# 08_IO.net
KiCad netlist of a schematic drawn in Altium Designer
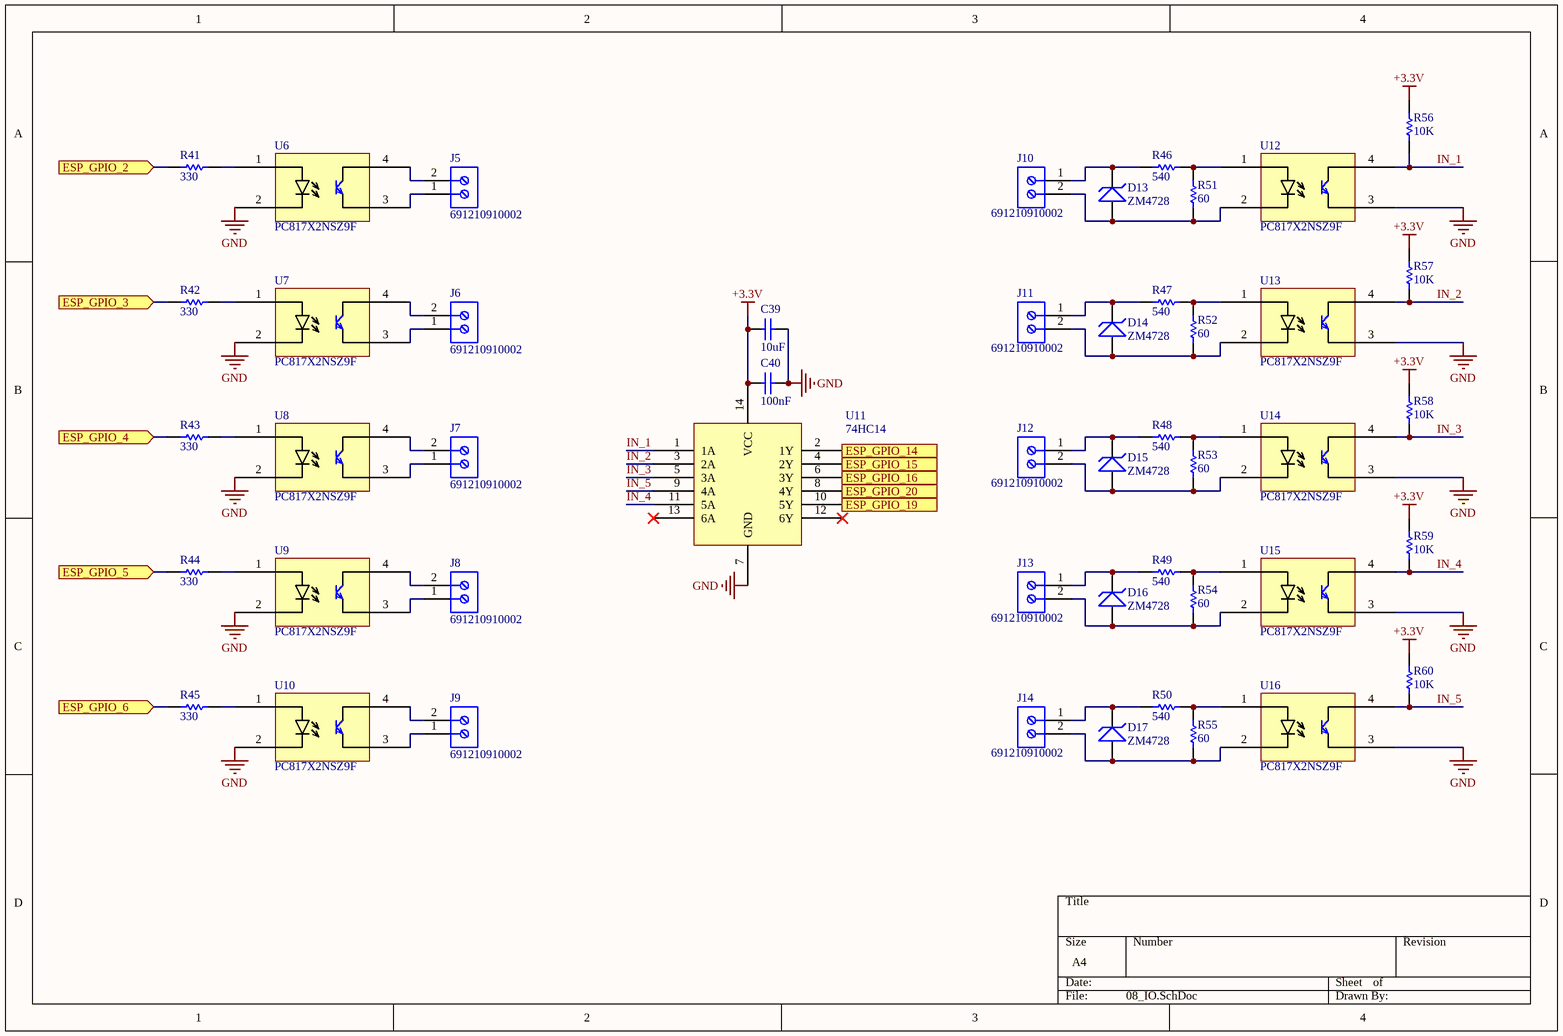
[diagram p0: 08_IO.SchDoc]

(export (version "E")
  (design (tool "Eeschema 10.0.6"))
  (components
    (comp (ref "C39")
      (value "10uF")
      (footprint "C0402")
      (fields (field (name "Comment") "Capacitor"))
      (libsource (lib "MiclsLib") (part "Capacitor"))
    )
    (comp (ref "C40")
      (value "100nF")
      (footprint "C0402")
      (fields (field (name "Comment") "Capacitor"))
      (libsource (lib "MiclsLib") (part "Capacitor"))
    )
    (comp (ref "D13")
      (value "ZM4728")
      (footprint "DIOMELF3515N")
      (libsource (lib "MiclsLib") (part "ZM4728"))
    )
    (comp (ref "D14")
      (value "ZM4728")
      (footprint "DIOMELF3515N")
      (libsource (lib "MiclsLib") (part "ZM4728"))
    )
    (comp (ref "D15")
      (value "ZM4728")
      (footprint "DIOMELF3515N")
      (libsource (lib "MiclsLib") (part "ZM4728"))
    )
    (comp (ref "D16")
      (value "ZM4728")
      (footprint "DIOMELF3515N")
      (libsource (lib "MiclsLib") (part "ZM4728"))
    )
    (comp (ref "D17")
      (value "ZM4728")
      (footprint "DIOMELF3515N")
      (libsource (lib "MiclsLib") (part "ZM4728"))
    )
    (comp (ref "J5")
      (value "691210910002")
      (footprint "691210910002")
      (description "WR-TBL Serie 2109 Horizontal Entry, Rising Cage Clamp, pitch 2.54mm, 2p")
      (fields (field (name "PUBLISHER") "Wurth Elektronik"))
      (libsource (lib "691322310002.") (part "691210910002"))
    )
    (comp (ref "J6")
      (value "691210910002")
      (footprint "691210910002")
      (description "WR-TBL Serie 2109 Horizontal Entry, Rising Cage Clamp, pitch 2.54mm, 2p")
      (fields (field (name "PUBLISHER") "Wurth Elektronik"))
      (libsource (lib "691322310002.") (part "691210910002"))
    )
    (comp (ref "J7")
      (value "691210910002")
      (footprint "691210910002")
      (description "WR-TBL Serie 2109 Horizontal Entry, Rising Cage Clamp, pitch 2.54mm, 2p")
      (fields (field (name "PUBLISHER") "Wurth Elektronik"))
      (libsource (lib "691322310002.") (part "691210910002"))
    )
    (comp (ref "J8")
      (value "691210910002")
      (footprint "691210910002")
      (description "WR-TBL Serie 2109 Horizontal Entry, Rising Cage Clamp, pitch 2.54mm, 2p")
      (fields (field (name "PUBLISHER") "Wurth Elektronik"))
      (libsource (lib "691322310002.") (part "691210910002"))
    )
    (comp (ref "J9")
      (value "691210910002")
      (footprint "691210910002")
      (description "WR-TBL Serie 2109 Horizontal Entry, Rising Cage Clamp, pitch 2.54mm, 2p")
      (fields (field (name "PUBLISHER") "Wurth Elektronik"))
      (libsource (lib "691322310002.") (part "691210910002"))
    )
    (comp (ref "J10")
      (value "691210910002")
      (footprint "691210910002")
      (description "WR-TBL Serie 2109 Horizontal Entry, Rising Cage Clamp, pitch 2.54mm, 2p")
      (fields (field (name "PUBLISHER") "Wurth Elektronik"))
      (libsource (lib "691322310002.") (part "691210910002"))
    )
    (comp (ref "J11")
      (value "691210910002")
      (footprint "691210910002")
      (description "WR-TBL Serie 2109 Horizontal Entry, Rising Cage Clamp, pitch 2.54mm, 2p")
      (fields (field (name "PUBLISHER") "Wurth Elektronik"))
      (libsource (lib "691322310002.") (part "691210910002"))
    )
    (comp (ref "J12")
      (value "691210910002")
      (footprint "691210910002")
      (description "WR-TBL Serie 2109 Horizontal Entry, Rising Cage Clamp, pitch 2.54mm, 2p")
      (fields (field (name "PUBLISHER") "Wurth Elektronik"))
      (libsource (lib "691322310002.") (part "691210910002"))
    )
    (comp (ref "J13")
      (value "691210910002")
      (footprint "691210910002")
      (description "WR-TBL Serie 2109 Horizontal Entry, Rising Cage Clamp, pitch 2.54mm, 2p")
      (fields (field (name "PUBLISHER") "Wurth Elektronik"))
      (libsource (lib "691322310002.") (part "691210910002"))
    )
    (comp (ref "J14")
      (value "691210910002")
      (footprint "691210910002")
      (description "WR-TBL Serie 2109 Horizontal Entry, Rising Cage Clamp, pitch 2.54mm, 2p")
      (fields (field (name "PUBLISHER") "Wurth Elektronik"))
      (libsource (lib "691322310002.") (part "691210910002"))
    )
    (comp (ref "R41")
      (value "330")
      (footprint "R0402")
      (fields (field (name "Comment") "Resistor"))
      (libsource (lib "MiclsLib") (part "Resistor"))
    )
    (comp (ref "R42")
      (value "330")
      (footprint "R0402")
      (fields (field (name "Comment") "Resistor"))
      (libsource (lib "MiclsLib") (part "Resistor"))
    )
    (comp (ref "R43")
      (value "330")
      (footprint "R0402")
      (fields (field (name "Comment") "Resistor"))
      (libsource (lib "MiclsLib") (part "Resistor"))
    )
    (comp (ref "R44")
      (value "330")
      (footprint "R0402")
      (fields (field (name "Comment") "Resistor"))
      (libsource (lib "MiclsLib") (part "Resistor"))
    )
    (comp (ref "R45")
      (value "330")
      (footprint "R0402")
      (fields (field (name "Comment") "Resistor"))
      (libsource (lib "MiclsLib") (part "Resistor"))
    )
    (comp (ref "R46")
      (value "540")
      (footprint "R0402")
      (fields (field (name "Comment") "Resistor"))
      (libsource (lib "MiclsLib") (part "Resistor"))
    )
    (comp (ref "R47")
      (value "540")
      (footprint "R0402")
      (fields (field (name "Comment") "Resistor"))
      (libsource (lib "MiclsLib") (part "Resistor"))
    )
    (comp (ref "R48")
      (value "540")
      (footprint "R0402")
      (fields (field (name "Comment") "Resistor"))
      (libsource (lib "MiclsLib") (part "Resistor"))
    )
    (comp (ref "R49")
      (value "540")
      (footprint "R0402")
      (fields (field (name "Comment") "Resistor"))
      (libsource (lib "MiclsLib") (part "Resistor"))
    )
    (comp (ref "R50")
      (value "540")
      (footprint "R0402")
      (fields (field (name "Comment") "Resistor"))
      (libsource (lib "MiclsLib") (part "Resistor"))
    )
    (comp (ref "R51")
      (value "60")
      (footprint "R0402")
      (fields (field (name "Comment") "Resistor"))
      (libsource (lib "MiclsLib") (part "Resistor"))
    )
    (comp (ref "R52")
      (value "60")
      (footprint "R0402")
      (fields (field (name "Comment") "Resistor"))
      (libsource (lib "MiclsLib") (part "Resistor"))
    )
    (comp (ref "R53")
      (value "60")
      (footprint "R0402")
      (fields (field (name "Comment") "Resistor"))
      (libsource (lib "MiclsLib") (part "Resistor"))
    )
    (comp (ref "R54")
      (value "60")
      (footprint "R0402")
      (fields (field (name "Comment") "Resistor"))
      (libsource (lib "MiclsLib") (part "Resistor"))
    )
    (comp (ref "R55")
      (value "60")
      (footprint "R0402")
      (fields (field (name "Comment") "Resistor"))
      (libsource (lib "MiclsLib") (part "Resistor"))
    )
    (comp (ref "R56")
      (value "10K")
      (footprint "R0402")
      (fields (field (name "Comment") "Resistor"))
      (libsource (lib "MiclsLib") (part "Resistor"))
    )
    (comp (ref "R57")
      (value "10K")
      (footprint "R0402")
      (fields (field (name "Comment") "Resistor"))
      (libsource (lib "MiclsLib") (part "Resistor"))
    )
    (comp (ref "R58")
      (value "10K")
      (footprint "R0402")
      (fields (field (name "Comment") "Resistor"))
      (libsource (lib "MiclsLib") (part "Resistor"))
    )
    (comp (ref "R59")
      (value "10K")
      (footprint "R0402")
      (fields (field (name "Comment") "Resistor"))
      (libsource (lib "MiclsLib") (part "Resistor"))
    )
    (comp (ref "R60")
      (value "10K")
      (footprint "R0402")
      (fields (field (name "Comment") "Resistor"))
      (libsource (lib "MiclsLib") (part "Resistor"))
    )
    (comp (ref "U6")
      (value "PC817X2NSZ9F")
      (footprint "PC817X2NSZ9F")
      (libsource (lib "MiclsLib") (part "PC817X2NSZ9F"))
    )
    (comp (ref "U7")
      (value "PC817X2NSZ9F")
      (footprint "PC817X2NSZ9F")
      (libsource (lib "MiclsLib") (part "PC817X2NSZ9F"))
    )
    (comp (ref "U8")
      (value "PC817X2NSZ9F")
      (footprint "PC817X2NSZ9F")
      (libsource (lib "MiclsLib") (part "PC817X2NSZ9F"))
    )
    (comp (ref "U9")
      (value "PC817X2NSZ9F")
      (footprint "PC817X2NSZ9F")
      (libsource (lib "MiclsLib") (part "PC817X2NSZ9F"))
    )
    (comp (ref "U10")
      (value "PC817X2NSZ9F")
      (footprint "PC817X2NSZ9F")
      (libsource (lib "MiclsLib") (part "PC817X2NSZ9F"))
    )
    (comp (ref "U11")
      (value "74HC14")
      (footprint "SOIC108P600X170-14N")
      (libsource (lib "MiclsLib") (part "74HC14"))
    )
    (comp (ref "U12")
      (value "PC817X2NSZ9F")
      (footprint "PC817X2NSZ9F")
      (libsource (lib "MiclsLib") (part "PC817X2NSZ9F"))
    )
    (comp (ref "U13")
      (value "PC817X2NSZ9F")
      (footprint "PC817X2NSZ9F")
      (libsource (lib "MiclsLib") (part "PC817X2NSZ9F"))
    )
    (comp (ref "U14")
      (value "PC817X2NSZ9F")
      (footprint "PC817X2NSZ9F")
      (libsource (lib "MiclsLib") (part "PC817X2NSZ9F"))
    )
    (comp (ref "U15")
      (value "PC817X2NSZ9F")
      (footprint "PC817X2NSZ9F")
      (libsource (lib "MiclsLib") (part "PC817X2NSZ9F"))
    )
    (comp (ref "U16")
      (value "PC817X2NSZ9F")
      (footprint "PC817X2NSZ9F")
      (libsource (lib "MiclsLib") (part "PC817X2NSZ9F"))
    )
  )
  (nets
    (net (code "1") (name "+3.3V") (class "Default")
      (node (ref "C39") (pin "1") (pinfunction "1_1") (pintype "passive"))
      (node (ref "C40") (pin "1") (pinfunction "1_1") (pintype "passive"))
      (node (ref "R56") (pin "2") (pinfunction "2_2") (pintype "passive"))
      (node (ref "R57") (pin "2") (pinfunction "2_2") (pintype "passive"))
      (node (ref "R58") (pin "2") (pinfunction "2_2") (pintype "passive"))
      (node (ref "R59") (pin "2") (pinfunction "2_2") (pintype "passive"))
      (node (ref "R60") (pin "2") (pinfunction "2_2") (pintype "passive"))
      (node (ref "U11") (pin "14") (pinfunction "VCC_14") (pintype "passive"))
    )
    (net (code "2") (name "/ESP_GPIO_2") (class "Default")
      (node (ref "R41") (pin "1") (pinfunction "1_1") (pintype "passive"))
    )
    (net (code "3") (name "/ESP_GPIO_3") (class "Default")
      (node (ref "R42") (pin "1") (pinfunction "1_1") (pintype "passive"))
    )
    (net (code "4") (name "/ESP_GPIO_4") (class "Default")
      (node (ref "R43") (pin "1") (pinfunction "1_1") (pintype "passive"))
    )
    (net (code "5") (name "/ESP_GPIO_5") (class "Default")
      (node (ref "R44") (pin "1") (pinfunction "1_1") (pintype "passive"))
    )
    (net (code "6") (name "/ESP_GPIO_6") (class "Default")
      (node (ref "R45") (pin "1") (pinfunction "1_1") (pintype "passive"))
    )
    (net (code "7") (name "/ESP_GPIO_14") (class "Default")
      (node (ref "U11") (pin "2") (pinfunction "1Y_2") (pintype "passive"))
    )
    (net (code "8") (name "/ESP_GPIO_15") (class "Default")
      (node (ref "U11") (pin "4") (pinfunction "2Y_4") (pintype "passive"))
    )
    (net (code "9") (name "/ESP_GPIO_16") (class "Default")
      (node (ref "U11") (pin "6") (pinfunction "3Y_6") (pintype "passive"))
    )
    (net (code "10") (name "/ESP_GPIO_19") (class "Default")
      (node (ref "U11") (pin "10") (pinfunction "5Y_10") (pintype "passive"))
    )
    (net (code "11") (name "/ESP_GPIO_20") (class "Default")
      (node (ref "U11") (pin "8") (pinfunction "4Y_8") (pintype "passive"))
    )
    (net (code "12") (name "/IN_1") (class "Default")
      (node (ref "R56") (pin "1") (pinfunction "1_1") (pintype "passive"))
      (node (ref "U11") (pin "1") (pinfunction "1A_1") (pintype "passive"))
      (node (ref "U12") (pin "4") (pinfunction "CATHODE_4") (pintype "passive"))
    )
    (net (code "13") (name "/IN_2") (class "Default")
      (node (ref "R57") (pin "1") (pinfunction "1_1") (pintype "passive"))
      (node (ref "U11") (pin "3") (pinfunction "2A_3") (pintype "passive"))
      (node (ref "U13") (pin "4") (pinfunction "CATHODE_4") (pintype "passive"))
    )
    (net (code "14") (name "/IN_3") (class "Default")
      (node (ref "R58") (pin "1") (pinfunction "1_1") (pintype "passive"))
      (node (ref "U11") (pin "5") (pinfunction "3A_5") (pintype "passive"))
      (node (ref "U14") (pin "4") (pinfunction "CATHODE_4") (pintype "passive"))
    )
    (net (code "15") (name "/IN_4") (class "Default")
      (node (ref "R59") (pin "1") (pinfunction "1_1") (pintype "passive"))
      (node (ref "U11") (pin "11") (pinfunction "5A_11") (pintype "passive"))
      (node (ref "U15") (pin "4") (pinfunction "CATHODE_4") (pintype "passive"))
    )
    (net (code "16") (name "/IN_5") (class "Default")
      (node (ref "R60") (pin "1") (pinfunction "1_1") (pintype "passive"))
      (node (ref "U11") (pin "9") (pinfunction "4A_9") (pintype "passive"))
      (node (ref "U16") (pin "4") (pinfunction "CATHODE_4") (pintype "passive"))
    )
    (net (code "17") (name "GND") (class "Default")
      (node (ref "C39") (pin "2") (pinfunction "2_2") (pintype "passive"))
      (node (ref "C40") (pin "2") (pinfunction "2_2") (pintype "passive"))
      (node (ref "U10") (pin "2") (pinfunction "CATHODE_2") (pintype "passive"))
      (node (ref "U11") (pin "7") (pinfunction "GND_7") (pintype "passive"))
      (node (ref "U12") (pin "3") (pinfunction "CATHODE_3") (pintype "passive"))
      (node (ref "U13") (pin "3") (pinfunction "CATHODE_3") (pintype "passive"))
      (node (ref "U14") (pin "3") (pinfunction "CATHODE_3") (pintype "passive"))
      (node (ref "U15") (pin "3") (pinfunction "CATHODE_3") (pintype "passive"))
      (node (ref "U16") (pin "3") (pinfunction "CATHODE_3") (pintype "passive"))
      (node (ref "U6") (pin "2") (pinfunction "CATHODE_2") (pintype "passive"))
      (node (ref "U7") (pin "2") (pinfunction "CATHODE_2") (pintype "passive"))
      (node (ref "U8") (pin "2") (pinfunction "CATHODE_2") (pintype "passive"))
      (node (ref "U9") (pin "2") (pinfunction "CATHODE_2") (pintype "passive"))
    )
    (net (code "18") (name "Net-(D13-Pad1)") (class "Default")
      (node (ref "D13") (pin "1") (pinfunction "1_1") (pintype "passive"))
      (node (ref "J10") (pin "1") (pinfunction "1_1") (pintype "passive"))
      (node (ref "R46") (pin "1") (pinfunction "1_1") (pintype "passive"))
    )
    (net (code "19") (name "Net-(D13-Pad2)") (class "Default")
      (node (ref "D13") (pin "2") (pinfunction "2_2") (pintype "passive"))
      (node (ref "J10") (pin "2") (pinfunction "2_2") (pintype "passive"))
      (node (ref "R51") (pin "1") (pinfunction "1_1") (pintype "passive"))
      (node (ref "U12") (pin "2") (pinfunction "CATHODE_2") (pintype "passive"))
    )
    (net (code "20") (name "Net-(D14-Pad1)") (class "Default")
      (node (ref "D14") (pin "1") (pinfunction "1_1") (pintype "passive"))
      (node (ref "J11") (pin "1") (pinfunction "1_1") (pintype "passive"))
      (node (ref "R47") (pin "1") (pinfunction "1_1") (pintype "passive"))
    )
    (net (code "21") (name "Net-(D14-Pad2)") (class "Default")
      (node (ref "D14") (pin "2") (pinfunction "2_2") (pintype "passive"))
      (node (ref "J11") (pin "2") (pinfunction "2_2") (pintype "passive"))
      (node (ref "R52") (pin "1") (pinfunction "1_1") (pintype "passive"))
      (node (ref "U13") (pin "2") (pinfunction "CATHODE_2") (pintype "passive"))
    )
    (net (code "22") (name "Net-(D15-Pad1)") (class "Default")
      (node (ref "D15") (pin "1") (pinfunction "1_1") (pintype "passive"))
      (node (ref "J12") (pin "1") (pinfunction "1_1") (pintype "passive"))
      (node (ref "R48") (pin "1") (pinfunction "1_1") (pintype "passive"))
    )
    (net (code "23") (name "Net-(D15-Pad2)") (class "Default")
      (node (ref "D15") (pin "2") (pinfunction "2_2") (pintype "passive"))
      (node (ref "J12") (pin "2") (pinfunction "2_2") (pintype "passive"))
      (node (ref "R53") (pin "1") (pinfunction "1_1") (pintype "passive"))
      (node (ref "U14") (pin "2") (pinfunction "CATHODE_2") (pintype "passive"))
    )
    (net (code "24") (name "Net-(D16-Pad1)") (class "Default")
      (node (ref "D16") (pin "1") (pinfunction "1_1") (pintype "passive"))
      (node (ref "J13") (pin "1") (pinfunction "1_1") (pintype "passive"))
      (node (ref "R49") (pin "1") (pinfunction "1_1") (pintype "passive"))
    )
    (net (code "25") (name "Net-(D16-Pad2)") (class "Default")
      (node (ref "D16") (pin "2") (pinfunction "2_2") (pintype "passive"))
      (node (ref "J13") (pin "2") (pinfunction "2_2") (pintype "passive"))
      (node (ref "R54") (pin "1") (pinfunction "1_1") (pintype "passive"))
      (node (ref "U15") (pin "2") (pinfunction "CATHODE_2") (pintype "passive"))
    )
    (net (code "26") (name "Net-(D17-Pad1)") (class "Default")
      (node (ref "D17") (pin "1") (pinfunction "1_1") (pintype "passive"))
      (node (ref "J14") (pin "1") (pinfunction "1_1") (pintype "passive"))
      (node (ref "R50") (pin "1") (pinfunction "1_1") (pintype "passive"))
    )
    (net (code "27") (name "Net-(D17-Pad2)") (class "Default")
      (node (ref "D17") (pin "2") (pinfunction "2_2") (pintype "passive"))
      (node (ref "J14") (pin "2") (pinfunction "2_2") (pintype "passive"))
      (node (ref "R55") (pin "1") (pinfunction "1_1") (pintype "passive"))
      (node (ref "U16") (pin "2") (pinfunction "CATHODE_2") (pintype "passive"))
    )
    (net (code "28") (name "Net-(J5-Pad1)") (class "Default")
      (node (ref "J5") (pin "1") (pinfunction "1_1") (pintype "passive"))
      (node (ref "U6") (pin "3") (pinfunction "CATHODE_3") (pintype "passive"))
    )
    (net (code "29") (name "Net-(J5-Pad2)") (class "Default")
      (node (ref "J5") (pin "2") (pinfunction "2_2") (pintype "passive"))
      (node (ref "U6") (pin "4") (pinfunction "CATHODE_4") (pintype "passive"))
    )
    (net (code "30") (name "Net-(J6-Pad1)") (class "Default")
      (node (ref "J6") (pin "1") (pinfunction "1_1") (pintype "passive"))
      (node (ref "U7") (pin "3") (pinfunction "CATHODE_3") (pintype "passive"))
    )
    (net (code "31") (name "Net-(J6-Pad2)") (class "Default")
      (node (ref "J6") (pin "2") (pinfunction "2_2") (pintype "passive"))
      (node (ref "U7") (pin "4") (pinfunction "CATHODE_4") (pintype "passive"))
    )
    (net (code "32") (name "Net-(J7-Pad1)") (class "Default")
      (node (ref "J7") (pin "1") (pinfunction "1_1") (pintype "passive"))
      (node (ref "U8") (pin "3") (pinfunction "CATHODE_3") (pintype "passive"))
    )
    (net (code "33") (name "Net-(J7-Pad2)") (class "Default")
      (node (ref "J7") (pin "2") (pinfunction "2_2") (pintype "passive"))
      (node (ref "U8") (pin "4") (pinfunction "CATHODE_4") (pintype "passive"))
    )
    (net (code "34") (name "Net-(J8-Pad1)") (class "Default")
      (node (ref "J8") (pin "1") (pinfunction "1_1") (pintype "passive"))
      (node (ref "U9") (pin "3") (pinfunction "CATHODE_3") (pintype "passive"))
    )
    (net (code "35") (name "Net-(J8-Pad2)") (class "Default")
      (node (ref "J8") (pin "2") (pinfunction "2_2") (pintype "passive"))
      (node (ref "U9") (pin "4") (pinfunction "CATHODE_4") (pintype "passive"))
    )
    (net (code "36") (name "Net-(J9-Pad1)") (class "Default")
      (node (ref "J9") (pin "1") (pinfunction "1_1") (pintype "passive"))
      (node (ref "U10") (pin "3") (pinfunction "CATHODE_3") (pintype "passive"))
    )
    (net (code "37") (name "Net-(J9-Pad2)") (class "Default")
      (node (ref "J9") (pin "2") (pinfunction "2_2") (pintype "passive"))
      (node (ref "U10") (pin "4") (pinfunction "CATHODE_4") (pintype "passive"))
    )
    (net (code "38") (name "Net-(U6-ANOTHE)") (class "Default")
      (node (ref "R41") (pin "2") (pinfunction "2_2") (pintype "passive"))
      (node (ref "U6") (pin "1") (pinfunction "ANOTHE_1") (pintype "passive"))
    )
    (net (code "39") (name "Net-(U7-ANOTHE)") (class "Default")
      (node (ref "R42") (pin "2") (pinfunction "2_2") (pintype "passive"))
      (node (ref "U7") (pin "1") (pinfunction "ANOTHE_1") (pintype "passive"))
    )
    (net (code "40") (name "Net-(U8-ANOTHE)") (class "Default")
      (node (ref "R43") (pin "2") (pinfunction "2_2") (pintype "passive"))
      (node (ref "U8") (pin "1") (pinfunction "ANOTHE_1") (pintype "passive"))
    )
    (net (code "41") (name "Net-(U9-ANOTHE)") (class "Default")
      (node (ref "R44") (pin "2") (pinfunction "2_2") (pintype "passive"))
      (node (ref "U9") (pin "1") (pinfunction "ANOTHE_1") (pintype "passive"))
    )
    (net (code "42") (name "Net-(U10-ANOTHE)") (class "Default")
      (node (ref "R45") (pin "2") (pinfunction "2_2") (pintype "passive"))
      (node (ref "U10") (pin "1") (pinfunction "ANOTHE_1") (pintype "passive"))
    )
    (net (code "43") (name "Net-(U12-ANOTHE)") (class "Default")
      (node (ref "R46") (pin "2") (pinfunction "2_2") (pintype "passive"))
      (node (ref "R51") (pin "2") (pinfunction "2_2") (pintype "passive"))
      (node (ref "U12") (pin "1") (pinfunction "ANOTHE_1") (pintype "passive"))
    )
    (net (code "44") (name "Net-(U13-ANOTHE)") (class "Default")
      (node (ref "R47") (pin "2") (pinfunction "2_2") (pintype "passive"))
      (node (ref "R52") (pin "2") (pinfunction "2_2") (pintype "passive"))
      (node (ref "U13") (pin "1") (pinfunction "ANOTHE_1") (pintype "passive"))
    )
    (net (code "45") (name "Net-(U14-ANOTHE)") (class "Default")
      (node (ref "R48") (pin "2") (pinfunction "2_2") (pintype "passive"))
      (node (ref "R53") (pin "2") (pinfunction "2_2") (pintype "passive"))
      (node (ref "U14") (pin "1") (pinfunction "ANOTHE_1") (pintype "passive"))
    )
    (net (code "46") (name "Net-(U15-ANOTHE)") (class "Default")
      (node (ref "R49") (pin "2") (pinfunction "2_2") (pintype "passive"))
      (node (ref "R54") (pin "2") (pinfunction "2_2") (pintype "passive"))
      (node (ref "U15") (pin "1") (pinfunction "ANOTHE_1") (pintype "passive"))
    )
    (net (code "47") (name "Net-(U16-ANOTHE)") (class "Default")
      (node (ref "R50") (pin "2") (pinfunction "2_2") (pintype "passive"))
      (node (ref "R55") (pin "2") (pinfunction "2_2") (pintype "passive"))
      (node (ref "U16") (pin "1") (pinfunction "ANOTHE_1") (pintype "passive"))
    )
    (net (code "48") (name "unconnected-(U11-6A-Pad13)") (class "Default")
      (node (ref "U11") (pin "13") (pinfunction "6A_13") (pintype "passive+no_connect"))
    )
    (net (code "49") (name "unconnected-(U11-6Y-Pad12)") (class "Default")
      (node (ref "U11") (pin "12") (pinfunction "6Y_12") (pintype "passive+no_connect"))
    )
  )
)
